# fanCtrl.net
KiCad netlist of a schematic drawn in EAGLE
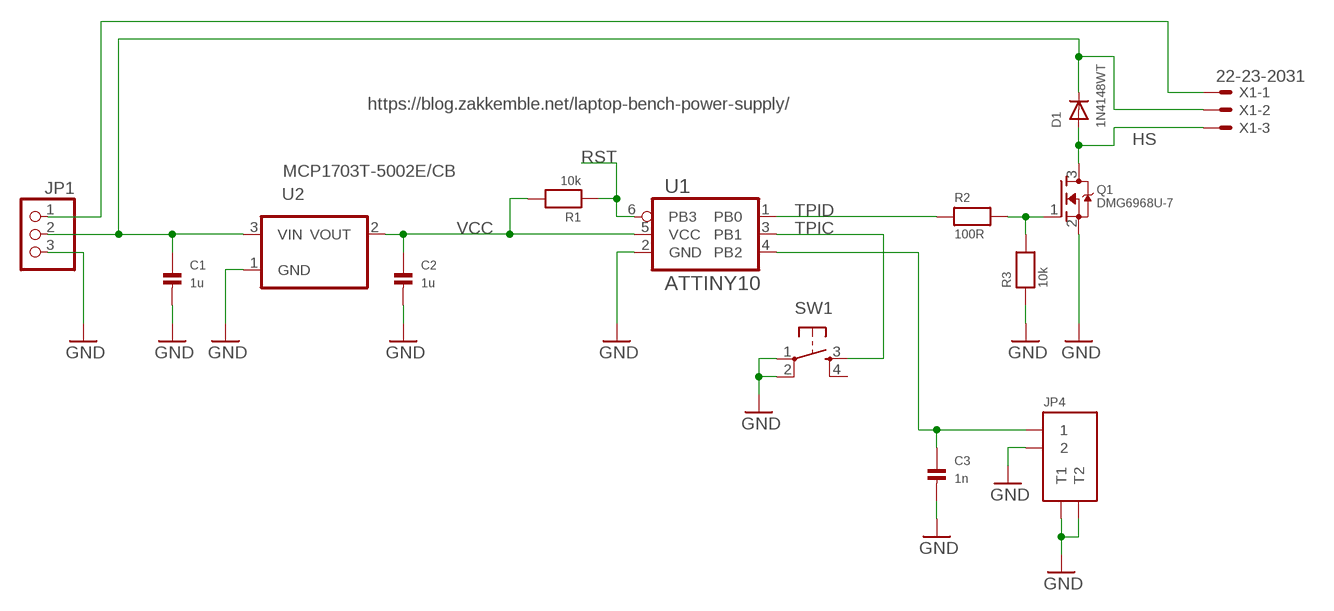
[diagram p0: schematic, sheet 1]

(export (version "E")
  (design (tool "Eeschema 10.0.6"))
  (components
    (comp (ref "C1")
      (value "1u")
      (footprint "eagle-import:_0603MP")
      (libsource (lib "eagle-import") (part "CAP_CERAMIC_0603MP"))
    )
    (comp (ref "C2")
      (value "1u")
      (footprint "eagle-import:_0603MP")
      (libsource (lib "eagle-import") (part "CAP_CERAMIC_0603MP"))
    )
    (comp (ref "C3")
      (value "1n")
      (footprint "eagle-import:0402_SMALL")
      (libsource (lib "eagle-import") (part "CAP_CERAMIC0402_SMALL"))
    )
    (comp (ref "D1")
      (value "1N4148WT")
      (footprint "eagle-import:SOD-523")
      (libsource (lib "eagle-import") (part "DIODESOD-523"))
    )
    (comp (ref "JP1")
      (value "PINHD-1X3")
      (footprint "eagle-import:1X03")
      (libsource (lib "eagle-import") (part "PINHD-1X3"))
    )
    (comp (ref "JP4")
      (value "2WAY")
      (footprint "eagle-import:2WAY")
      (libsource (lib "eagle-import") (part "2WAY"))
    )
    (comp (ref "Q1")
      (value "DMG6968U-7")
      (footprint "eagle-import:SOT23-W")
      (libsource (lib "eagle-import") (part "MOSFET-NWAVE"))
    )
    (comp (ref "R1")
      (value "10k")
      (footprint "eagle-import:0402_SMALL")
      (libsource (lib "eagle-import") (part "RESISTOR0402_SMALL"))
    )
    (comp (ref "R2")
      (value "100R")
      (footprint "eagle-import:0402_SMALL")
      (libsource (lib "eagle-import") (part "RESISTOR0402_SMALL"))
    )
    (comp (ref "R3")
      (value "10k")
      (footprint "eagle-import:0402_SMALL")
      (libsource (lib "eagle-import") (part "RESISTOR0402_SMALL"))
    )
    (comp (ref "SW1")
      (value "SPST_TACTG75_3X4")
      (footprint "eagle-import:TACT_SMD5")
      (libsource (lib "eagle-import") (part "SPST_TACTG75_3X4"))
    )
    (comp (ref "U1")
      (value "ATTINY10")
      (footprint "eagle-import:SOT23-6_SM_PAD")
      (libsource (lib "eagle-import") (part "ATTINY10SM_PAD"))
    )
    (comp (ref "U2")
      (value "MCP1703T-5002E/CB")
      (footprint "eagle-import:SOT-23")
      (libsource (lib "eagle-import") (part "MCP1700T-2502E/TTWIDE_PAD"))
    )
    (comp (ref "X1")
      (value "22-23-2031")
      (footprint "eagle-import:22-23-2031")
      (fields (field (name "MF") "MOLEX"))
      (libsource (lib "eagle-import") (part "22-23-2031"))
    )
  )
  (nets
    (net (code "1") (name "/HS") (class "Default")
      (node (ref "D1") (pin "A") (pinfunction "A_A") (pintype "passive"))
      (node (ref "Q1") (pin "3") (pinfunction "D_3") (pintype "bidirectional"))
      (node (ref "X1") (pin "3") (pinfunction "S_3") (pintype "passive"))
    )
    (net (code "2") (name "/RST") (class "Default")
      (node (ref "R1") (pin "1") (pinfunction "1_1") (pintype "passive"))
      (node (ref "U1") (pin "6") (pinfunction "PB3_6") (pintype "bidirectional"))
    )
    (net (code "3") (name "/TPIC") (class "Default")
      (node (ref "SW1") (pin "3") (pinfunction "S_3") (pintype "passive"))
      (node (ref "U1") (pin "3") (pinfunction "PB1_3") (pintype "bidirectional"))
    )
    (net (code "4") (name "/TPID") (class "Default")
      (node (ref "R2") (pin "1") (pinfunction "1_1") (pintype "passive"))
      (node (ref "U1") (pin "1") (pinfunction "PB0_1") (pintype "bidirectional"))
    )
    (net (code "5") (name "/VCC") (class "Default")
      (node (ref "C2") (pin "1") (pinfunction "P$1_1") (pintype "passive"))
      (node (ref "R1") (pin "2") (pinfunction "2_2") (pintype "passive"))
      (node (ref "U1") (pin "5") (pinfunction "VCC_5") (pintype "power_in"))
      (node (ref "U2") (pin "2") (pinfunction "VOUT_2") (pintype "output"))
    )
    (net (code "6") (name "GND") (class "Default")
      (node (ref "C1") (pin "2") (pinfunction "P$2_2") (pintype "passive"))
      (node (ref "C2") (pin "2") (pinfunction "P$2_2") (pintype "passive"))
      (node (ref "C3") (pin "2") (pinfunction "P$2_2") (pintype "passive"))
      (node (ref "JP1") (pin "3") (pinfunction "3_3") (pintype "passive"))
      (node (ref "JP4") (pin "P$2") (pinfunction "2_P$2") (pintype "passive"))
      (node (ref "JP4") (pin "TAB$1") (pinfunction "T1_TAB$1") (pintype "passive"))
      (node (ref "JP4") (pin "TAB$2") (pinfunction "T2_TAB$2") (pintype "passive"))
      (node (ref "Q1") (pin "2") (pinfunction "S_2") (pintype "bidirectional"))
      (node (ref "R3") (pin "1") (pinfunction "1_1") (pintype "passive"))
      (node (ref "SW1") (pin "1") (pinfunction "P_1") (pintype "passive"))
      (node (ref "SW1") (pin "2") (pinfunction "P1_2") (pintype "passive"))
      (node (ref "U1") (pin "2") (pinfunction "GND_2") (pintype "passive"))
      (node (ref "U2") (pin "1") (pinfunction "GND_1") (pintype "passive"))
    )
    (net (code "7") (name "Net-(C1-P$1)") (class "Default")
      (node (ref "C1") (pin "1") (pinfunction "P$1_1") (pintype "passive"))
      (node (ref "D1") (pin "K") (pinfunction "C_K") (pintype "passive"))
      (node (ref "JP1") (pin "2") (pinfunction "2_2") (pintype "passive"))
      (node (ref "U2") (pin "3") (pinfunction "VIN_3") (pintype "power_in"))
      (node (ref "X1") (pin "2") (pinfunction "S_2") (pintype "passive"))
    )
    (net (code "8") (name "Net-(C3-P$1)") (class "Default")
      (node (ref "C3") (pin "1") (pinfunction "P$1_1") (pintype "passive"))
      (node (ref "JP4") (pin "P$1") (pinfunction "1_P$1") (pintype "passive"))
      (node (ref "U1") (pin "4") (pinfunction "PB2_4") (pintype "bidirectional"))
    )
    (net (code "9") (name "Net-(Q1-G)") (class "Default")
      (node (ref "Q1") (pin "1") (pinfunction "G_1") (pintype "bidirectional"))
      (node (ref "R2") (pin "2") (pinfunction "2_2") (pintype "passive"))
      (node (ref "R3") (pin "2") (pinfunction "2_2") (pintype "passive"))
    )
    (net (code "10") (name "Net-(X1A-S)") (class "Default")
      (node (ref "JP1") (pin "1") (pinfunction "1_1") (pintype "passive"))
      (node (ref "X1") (pin "1") (pinfunction "S_1") (pintype "passive"))
    )
    (net (code "11") (name "unconnected-(SW1-S1-Pad4)") (class "Default")
      (node (ref "SW1") (pin "4") (pinfunction "S1_4") (pintype "passive"))
    )
  )
)
